# raspberry.net
KiCad netlist of a schematic drawn in EAGLE
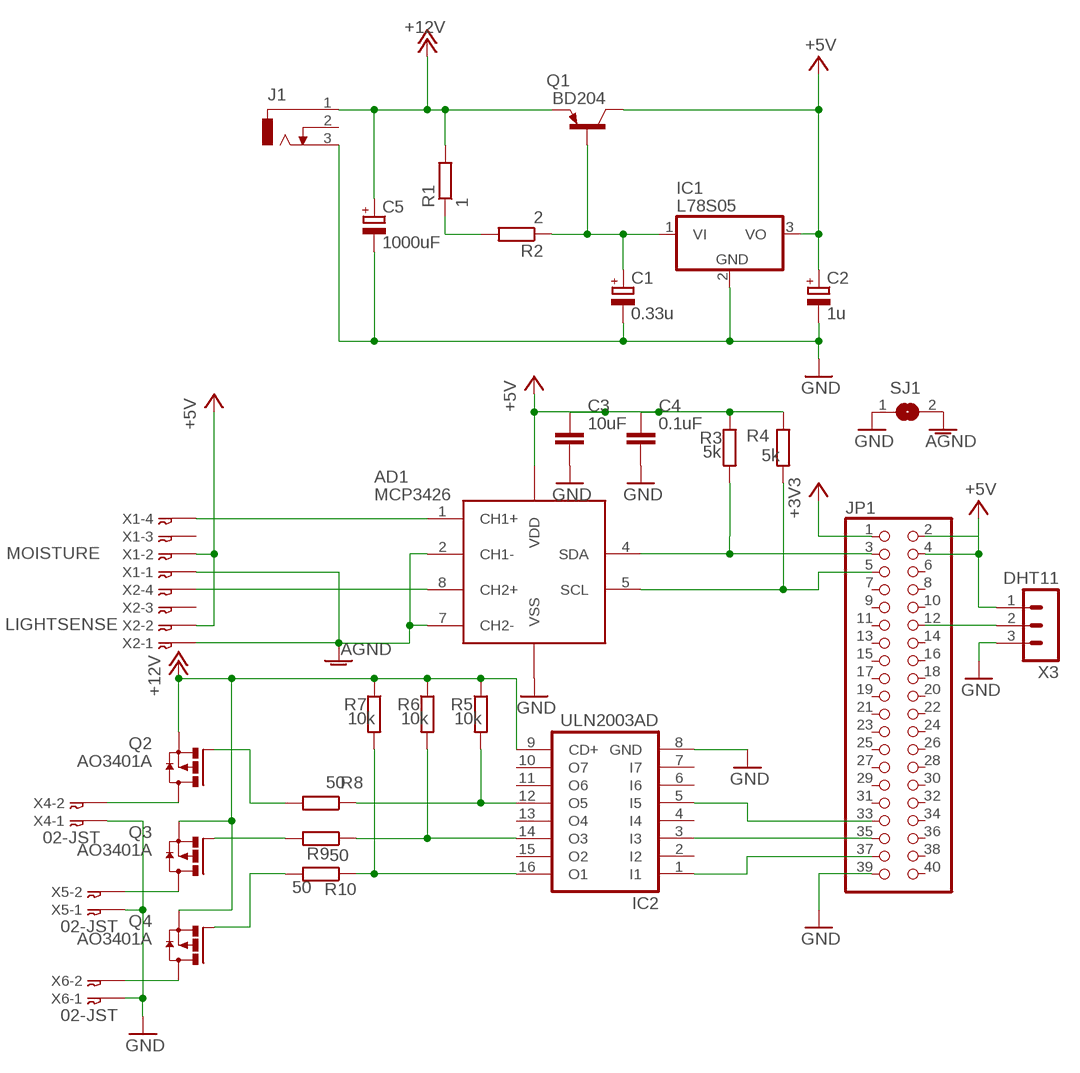
[diagram p0: schematic, sheet 1]

(export (version "E")
  (design (tool "Eeschema 10.0.6"))
  (components
    (comp (ref "AD1")
      (value "MCP3426")
      (footprint "eagle-import:SO-8")
      (libsource (lib "eagle-import") (part "MCP3426A0-E/SN"))
    )
    (comp (ref "C1")
      (value "0.33u")
      (footprint "eagle-import:E1,8-4")
      (libsource (lib "eagle-import") (part "CPOL-EUE1.8-4"))
    )
    (comp (ref "C2")
      (value "1u")
      (footprint "eagle-import:E2-4")
      (libsource (lib "eagle-import") (part "CPOL-EUE2-4"))
    )
    (comp (ref "C3")
      (value "10uF")
      (footprint "eagle-import:CAPM3216X180")
      (libsource (lib "eagle-import") (part "CTANTALUM-1206(3216-METRIC)_"))
    )
    (comp (ref "C4")
      (value "0.1uF")
      (footprint "eagle-import:CAPC2012X110")
      (libsource (lib "eagle-import") (part "CCHIP-0805(2012-METRIC)_"))
    )
    (comp (ref "C5")
      (value "1000uF")
      (footprint "eagle-import:E5-13")
      (libsource (lib "eagle-import") (part "CPOL-EUE5-13"))
    )
    (comp (ref "IC1")
      (value "L78S05")
      (footprint "eagle-import:TO220V")
      (libsource (lib "eagle-import") (part "78TV05"))
    )
    (comp (ref "IC2")
      (value "ULN2003AD")
      (footprint "eagle-import:SO16")
      (libsource (lib "eagle-import") (part "ULN2003AD"))
    )
    (comp (ref "J1")
      (value "DCJ0303")
      (footprint "eagle-import:DCJ0303")
      (libsource (lib "eagle-import") (part "DCJ0303"))
    )
    (comp (ref "JP1")
      (value "PINHD-2X20")
      (footprint "eagle-import:2X20")
      (libsource (lib "eagle-import") (part "PINHD-2X20"))
    )
    (comp (ref "Q1")
      (value "BD204")
      (footprint "eagle-import:TO220V")
      (libsource (lib "eagle-import") (part "-PNP-TO220V"))
    )
    (comp (ref "Q2")
      (value "AO3401A")
      (footprint "eagle-import:SOT23")
      (libsource (lib "eagle-import") (part "AO3401A"))
    )
    (comp (ref "Q3")
      (value "AO3401A")
      (footprint "eagle-import:SOT23")
      (libsource (lib "eagle-import") (part "AO3401A"))
    )
    (comp (ref "Q4")
      (value "AO3401A")
      (footprint "eagle-import:SOT23")
      (libsource (lib "eagle-import") (part "AO3401A"))
    )
    (comp (ref "R1")
      (value "1")
      (footprint "eagle-import:R0805W")
      (libsource (lib "eagle-import") (part "R-EU_R0805W"))
    )
    (comp (ref "R2")
      (value "2")
      (footprint "eagle-import:R0805W")
      (libsource (lib "eagle-import") (part "R-EU_R0805W"))
    )
    (comp (ref "R3")
      (value "5k")
      (footprint "eagle-import:R0805W")
      (libsource (lib "eagle-import") (part "R-EU_R0805W"))
    )
    (comp (ref "R4")
      (value "5k")
      (footprint "eagle-import:R0805W")
      (libsource (lib "eagle-import") (part "R-EU_R0805W"))
    )
    (comp (ref "R5")
      (value "10k")
      (footprint "eagle-import:R0805W")
      (libsource (lib "eagle-import") (part "R-EU_R0805W"))
    )
    (comp (ref "R6")
      (value "10k")
      (footprint "eagle-import:R0805W")
      (libsource (lib "eagle-import") (part "R-EU_R0805W"))
    )
    (comp (ref "R7")
      (value "10k")
      (footprint "eagle-import:R0805W")
      (libsource (lib "eagle-import") (part "R-EU_R0805W"))
    )
    (comp (ref "R8")
      (value "50")
      (footprint "eagle-import:R0805W")
      (libsource (lib "eagle-import") (part "R-EU_R0805W"))
    )
    (comp (ref "R9")
      (value "50")
      (footprint "eagle-import:R0805W")
      (libsource (lib "eagle-import") (part "R-EU_R0805W"))
    )
    (comp (ref "R10")
      (value "50")
      (footprint "eagle-import:R0805W")
      (libsource (lib "eagle-import") (part "R-EU_R0805W"))
    )
    (comp (ref "SJ1") (value "SJ") (footprint "eagle-import:SJ") (libsource (lib "eagle-import") (part "SJ")))
    (comp (ref "X1")
      (value "MOISTURE")
      (footprint "eagle-import:B4B-XH")
      (libsource (lib "eagle-import") (part "04-JST-B4B-XH-A"))
    )
    (comp (ref "X2")
      (value "LIGHTSENSE")
      (footprint "eagle-import:B4B-XH")
      (libsource (lib "eagle-import") (part "04-JST-B4B-XH-A"))
    )
    (comp (ref "X3")
      (value "DHT11")
      (footprint "eagle-import:MA03-1")
      (libsource (lib "eagle-import") (part "MA03-1"))
    )
    (comp (ref "X4")
      (value "02-JST")
      (footprint "eagle-import:B2B-XH")
      (libsource (lib "eagle-import") (part "02-JST"))
    )
    (comp (ref "X5")
      (value "02-JST")
      (footprint "eagle-import:B2B-XH")
      (libsource (lib "eagle-import") (part "02-JST"))
    )
    (comp (ref "X6")
      (value "02-JST")
      (footprint "eagle-import:B2B-XH")
      (libsource (lib "eagle-import") (part "02-JST"))
    )
  )
  (nets
    (net (code "1") (name "+3V3") (class "Default")
      (node (ref "JP1") (pin "1") (pinfunction "1_1") (pintype "passive"))
    )
    (net (code "2") (name "+5V") (class "Default")
      (node (ref "AD1") (pin "3") (pinfunction "VDD_3") (pintype "power_in"))
      (node (ref "C2") (pin "+") (pinfunction "+_+") (pintype "passive"))
      (node (ref "C3") (pin "1") (pinfunction "1_1") (pintype "passive"))
      (node (ref "C4") (pin "1") (pinfunction "1_1") (pintype "passive"))
      (node (ref "IC1") (pin "3") (pinfunction "VO_3") (pintype "passive"))
      (node (ref "JP1") (pin "2") (pinfunction "2_2") (pintype "passive"))
      (node (ref "JP1") (pin "4") (pinfunction "4_4") (pintype "passive"))
      (node (ref "Q1") (pin "2") (pinfunction "C_2") (pintype "passive"))
      (node (ref "R3") (pin "1") (pinfunction "1_1") (pintype "passive"))
      (node (ref "R4") (pin "1") (pinfunction "1_1") (pintype "passive"))
      (node (ref "X1") (pin "P$2") (pinfunction "1_P$2") (pintype "passive"))
      (node (ref "X2") (pin "P$2") (pinfunction "1_P$2") (pintype "passive"))
      (node (ref "X3") (pin "1") (pinfunction "1_1") (pintype "passive"))
    )
    (net (code "3") (name "+12V") (class "Default")
      (node (ref "C5") (pin "+") (pinfunction "+_+") (pintype "passive"))
      (node (ref "IC2") (pin "9") (pinfunction "CD+_9") (pintype "passive"))
      (node (ref "J1") (pin "1") (pinfunction "1_1") (pintype "passive"))
      (node (ref "Q1") (pin "3") (pinfunction "E_3") (pintype "passive"))
      (node (ref "Q2") (pin "2") (pinfunction "S_2") (pintype "passive"))
      (node (ref "Q3") (pin "2") (pinfunction "S_2") (pintype "passive"))
      (node (ref "Q4") (pin "2") (pinfunction "S_2") (pintype "passive"))
      (node (ref "R1") (pin "2") (pinfunction "2_2") (pintype "passive"))
      (node (ref "R5") (pin "1") (pinfunction "1_1") (pintype "passive"))
      (node (ref "R6") (pin "1") (pinfunction "1_1") (pintype "passive"))
      (node (ref "R7") (pin "1") (pinfunction "1_1") (pintype "passive"))
    )
    (net (code "4") (name "AGND") (class "Default")
      (node (ref "AD1") (pin "2") (pinfunction "CH1-_2") (pintype "bidirectional"))
      (node (ref "AD1") (pin "7") (pinfunction "CH2-_7") (pintype "bidirectional"))
      (node (ref "SJ1") (pin "2") (pinfunction "2_2") (pintype "passive"))
      (node (ref "X1") (pin "P$1") (pinfunction "1_P$1") (pintype "passive"))
      (node (ref "X2") (pin "P$1") (pinfunction "1_P$1") (pintype "passive"))
    )
    (net (code "5") (name "GND") (class "Default")
      (node (ref "AD1") (pin "6") (pinfunction "VSS_6") (pintype "power_in"))
      (node (ref "C1") (pin "-") (pinfunction "-_-") (pintype "passive"))
      (node (ref "C2") (pin "-") (pinfunction "-_-") (pintype "passive"))
      (node (ref "C3") (pin "2") (pinfunction "2_2") (pintype "passive"))
      (node (ref "C4") (pin "2") (pinfunction "2_2") (pintype "passive"))
      (node (ref "C5") (pin "-") (pinfunction "-_-") (pintype "passive"))
      (node (ref "IC1") (pin "2") (pinfunction "GND_2") (pintype "passive"))
      (node (ref "IC2") (pin "8") (pinfunction "GND_8") (pintype "power_in"))
      (node (ref "J1") (pin "3") (pinfunction "3_3") (pintype "passive"))
      (node (ref "JP1") (pin "39") (pinfunction "39_39") (pintype "passive"))
      (node (ref "SJ1") (pin "1") (pinfunction "1_1") (pintype "passive"))
      (node (ref "X3") (pin "3") (pinfunction "3_3") (pintype "passive"))
      (node (ref "X4") (pin "P$1") (pinfunction "1_P$1") (pintype "passive"))
      (node (ref "X5") (pin "P$1") (pinfunction "1_P$1") (pintype "passive"))
      (node (ref "X6") (pin "P$1") (pinfunction "1_P$1") (pintype "passive"))
    )
    (net (code "6") (name "Net-(AD1-CH1+)") (class "Default")
      (node (ref "AD1") (pin "1") (pinfunction "CH1+_1") (pintype "bidirectional"))
      (node (ref "X1") (pin "P$4") (pinfunction "1_P$4") (pintype "passive"))
    )
    (net (code "7") (name "Net-(AD1-CH2+)") (class "Default")
      (node (ref "AD1") (pin "8") (pinfunction "CH2+_8") (pintype "bidirectional"))
      (node (ref "X2") (pin "P$4") (pinfunction "1_P$4") (pintype "passive"))
    )
    (net (code "8") (name "Net-(AD1-SCL)") (class "Default")
      (node (ref "AD1") (pin "5") (pinfunction "SCL_5") (pintype "bidirectional"))
      (node (ref "JP1") (pin "5") (pinfunction "5_5") (pintype "passive"))
      (node (ref "R4") (pin "2") (pinfunction "2_2") (pintype "passive"))
    )
    (net (code "9") (name "Net-(AD1-SDA)") (class "Default")
      (node (ref "AD1") (pin "4") (pinfunction "SDA_4") (pintype "bidirectional"))
      (node (ref "JP1") (pin "3") (pinfunction "3_3") (pintype "passive"))
      (node (ref "R3") (pin "2") (pinfunction "2_2") (pintype "passive"))
    )
    (net (code "10") (name "Net-(IC1-VI)") (class "Default")
      (node (ref "C1") (pin "+") (pinfunction "+_+") (pintype "passive"))
      (node (ref "IC1") (pin "1") (pinfunction "VI_1") (pintype "input"))
      (node (ref "Q1") (pin "1") (pinfunction "B_1") (pintype "passive"))
      (node (ref "R2") (pin "1") (pinfunction "1_1") (pintype "passive"))
    )
    (net (code "11") (name "Net-(IC2-I1)") (class "Default")
      (node (ref "IC2") (pin "1") (pinfunction "I1_1") (pintype "input"))
      (node (ref "JP1") (pin "37") (pinfunction "37_37") (pintype "passive"))
    )
    (net (code "12") (name "Net-(IC2-I3)") (class "Default")
      (node (ref "IC2") (pin "3") (pinfunction "I3_3") (pintype "input"))
      (node (ref "JP1") (pin "35") (pinfunction "35_35") (pintype "passive"))
    )
    (net (code "13") (name "Net-(IC2-I5)") (class "Default")
      (node (ref "IC2") (pin "5") (pinfunction "I5_5") (pintype "input"))
      (node (ref "JP1") (pin "33") (pinfunction "33_33") (pintype "passive"))
    )
    (net (code "14") (name "Net-(IC2-O1)") (class "Default")
      (node (ref "IC2") (pin "16") (pinfunction "O1_16") (pintype "open_collector"))
      (node (ref "R10") (pin "1") (pinfunction "1_1") (pintype "passive"))
      (node (ref "R7") (pin "2") (pinfunction "2_2") (pintype "passive"))
    )
    (net (code "15") (name "Net-(IC2-O3)") (class "Default")
      (node (ref "IC2") (pin "14") (pinfunction "O3_14") (pintype "open_collector"))
      (node (ref "R6") (pin "2") (pinfunction "2_2") (pintype "passive"))
      (node (ref "R9") (pin "1") (pinfunction "1_1") (pintype "passive"))
    )
    (net (code "16") (name "Net-(IC2-O5)") (class "Default")
      (node (ref "IC2") (pin "12") (pinfunction "O5_12") (pintype "open_collector"))
      (node (ref "R5") (pin "2") (pinfunction "2_2") (pintype "passive"))
      (node (ref "R8") (pin "1") (pinfunction "1_1") (pintype "passive"))
    )
    (net (code "17") (name "Net-(JP1-Pad12)") (class "Default")
      (node (ref "JP1") (pin "12") (pinfunction "12_12") (pintype "passive"))
      (node (ref "X3") (pin "2") (pinfunction "2_2") (pintype "passive"))
    )
    (net (code "18") (name "Net-(Q2-D)") (class "Default")
      (node (ref "Q2") (pin "3") (pinfunction "D_3") (pintype "passive"))
      (node (ref "X4") (pin "P$2") (pinfunction "1_P$2") (pintype "passive"))
    )
    (net (code "19") (name "Net-(Q2-G)") (class "Default")
      (node (ref "Q2") (pin "1") (pinfunction "G_1") (pintype "passive"))
      (node (ref "R8") (pin "2") (pinfunction "2_2") (pintype "passive"))
    )
    (net (code "20") (name "Net-(Q3-D)") (class "Default")
      (node (ref "Q3") (pin "3") (pinfunction "D_3") (pintype "passive"))
      (node (ref "X5") (pin "P$2") (pinfunction "1_P$2") (pintype "passive"))
    )
    (net (code "21") (name "Net-(Q3-G)") (class "Default")
      (node (ref "Q3") (pin "1") (pinfunction "G_1") (pintype "passive"))
      (node (ref "R9") (pin "2") (pinfunction "2_2") (pintype "passive"))
    )
    (net (code "22") (name "Net-(Q4-D)") (class "Default")
      (node (ref "Q4") (pin "3") (pinfunction "D_3") (pintype "passive"))
      (node (ref "X6") (pin "P$2") (pinfunction "1_P$2") (pintype "passive"))
    )
    (net (code "23") (name "Net-(Q4-G)") (class "Default")
      (node (ref "Q4") (pin "1") (pinfunction "G_1") (pintype "passive"))
      (node (ref "R10") (pin "2") (pinfunction "2_2") (pintype "passive"))
    )
    (net (code "24") (name "Net-(R1-Pad1)") (class "Default")
      (node (ref "R1") (pin "1") (pinfunction "1_1") (pintype "passive"))
      (node (ref "R2") (pin "2") (pinfunction "2_2") (pintype "passive"))
    )
    (net (code "25") (name "unconnected-(IC2-I2-Pad2)") (class "Default")
      (node (ref "IC2") (pin "2") (pinfunction "I2_2") (pintype "input"))
    )
    (net (code "26") (name "unconnected-(IC2-I4-Pad4)") (class "Default")
      (node (ref "IC2") (pin "4") (pinfunction "I4_4") (pintype "input"))
    )
    (net (code "27") (name "unconnected-(IC2-I6-Pad6)") (class "Default")
      (node (ref "IC2") (pin "6") (pinfunction "I6_6") (pintype "input"))
    )
    (net (code "28") (name "unconnected-(IC2-I7-Pad7)") (class "Default")
      (node (ref "IC2") (pin "7") (pinfunction "I7_7") (pintype "input"))
    )
    (net (code "29") (name "unconnected-(IC2-O2-Pad15)") (class "Default")
      (node (ref "IC2") (pin "15") (pinfunction "O2_15") (pintype "open_collector"))
    )
    (net (code "30") (name "unconnected-(IC2-O4-Pad13)") (class "Default")
      (node (ref "IC2") (pin "13") (pinfunction "O4_13") (pintype "open_collector"))
    )
    (net (code "31") (name "unconnected-(IC2-O6-Pad11)") (class "Default")
      (node (ref "IC2") (pin "11") (pinfunction "O6_11") (pintype "open_collector"))
    )
    (net (code "32") (name "unconnected-(IC2-O7-Pad10)") (class "Default")
      (node (ref "IC2") (pin "10") (pinfunction "O7_10") (pintype "open_collector"))
    )
    (net (code "33") (name "unconnected-(J1-Pad2)") (class "Default")
      (node (ref "J1") (pin "2") (pinfunction "2_2") (pintype "passive"))
    )
    (net (code "34") (name "unconnected-(JP1-Pad6)") (class "Default")
      (node (ref "JP1") (pin "6") (pinfunction "6_6") (pintype "passive"))
    )
    (net (code "35") (name "unconnected-(JP1-Pad7)") (class "Default")
      (node (ref "JP1") (pin "7") (pinfunction "7_7") (pintype "passive"))
    )
    (net (code "36") (name "unconnected-(JP1-Pad8)") (class "Default")
      (node (ref "JP1") (pin "8") (pinfunction "8_8") (pintype "passive"))
    )
    (net (code "37") (name "unconnected-(JP1-Pad9)") (class "Default")
      (node (ref "JP1") (pin "9") (pinfunction "9_9") (pintype "passive"))
    )
    (net (code "38") (name "unconnected-(JP1-Pad10)") (class "Default")
      (node (ref "JP1") (pin "10") (pinfunction "10_10") (pintype "passive"))
    )
    (net (code "39") (name "unconnected-(JP1-Pad11)") (class "Default")
      (node (ref "JP1") (pin "11") (pinfunction "11_11") (pintype "passive"))
    )
    (net (code "40") (name "unconnected-(JP1-Pad13)") (class "Default")
      (node (ref "JP1") (pin "13") (pinfunction "13_13") (pintype "passive"))
    )
    (net (code "41") (name "unconnected-(JP1-Pad14)") (class "Default")
      (node (ref "JP1") (pin "14") (pinfunction "14_14") (pintype "passive"))
    )
    (net (code "42") (name "unconnected-(JP1-Pad15)") (class "Default")
      (node (ref "JP1") (pin "15") (pinfunction "15_15") (pintype "passive"))
    )
    (net (code "43") (name "unconnected-(JP1-Pad16)") (class "Default")
      (node (ref "JP1") (pin "16") (pinfunction "16_16") (pintype "passive"))
    )
    (net (code "44") (name "unconnected-(JP1-Pad17)") (class "Default")
      (node (ref "JP1") (pin "17") (pinfunction "17_17") (pintype "passive"))
    )
    (net (code "45") (name "unconnected-(JP1-Pad18)") (class "Default")
      (node (ref "JP1") (pin "18") (pinfunction "18_18") (pintype "passive"))
    )
    (net (code "46") (name "unconnected-(JP1-Pad19)") (class "Default")
      (node (ref "JP1") (pin "19") (pinfunction "19_19") (pintype "passive"))
    )
    (net (code "47") (name "unconnected-(JP1-Pad20)") (class "Default")
      (node (ref "JP1") (pin "20") (pinfunction "20_20") (pintype "passive"))
    )
    (net (code "48") (name "unconnected-(JP1-Pad21)") (class "Default")
      (node (ref "JP1") (pin "21") (pinfunction "21_21") (pintype "passive"))
    )
    (net (code "49") (name "unconnected-(JP1-Pad22)") (class "Default")
      (node (ref "JP1") (pin "22") (pinfunction "22_22") (pintype "passive"))
    )
    (net (code "50") (name "unconnected-(JP1-Pad23)") (class "Default")
      (node (ref "JP1") (pin "23") (pinfunction "23_23") (pintype "passive"))
    )
    (net (code "51") (name "unconnected-(JP1-Pad24)") (class "Default")
      (node (ref "JP1") (pin "24") (pinfunction "24_24") (pintype "passive"))
    )
    (net (code "52") (name "unconnected-(JP1-Pad25)") (class "Default")
      (node (ref "JP1") (pin "25") (pinfunction "25_25") (pintype "passive"))
    )
    (net (code "53") (name "unconnected-(JP1-Pad26)") (class "Default")
      (node (ref "JP1") (pin "26") (pinfunction "26_26") (pintype "passive"))
    )
    (net (code "54") (name "unconnected-(JP1-Pad27)") (class "Default")
      (node (ref "JP1") (pin "27") (pinfunction "27_27") (pintype "passive"))
    )
    (net (code "55") (name "unconnected-(JP1-Pad28)") (class "Default")
      (node (ref "JP1") (pin "28") (pinfunction "28_28") (pintype "passive"))
    )
    (net (code "56") (name "unconnected-(JP1-Pad29)") (class "Default")
      (node (ref "JP1") (pin "29") (pinfunction "29_29") (pintype "passive"))
    )
    (net (code "57") (name "unconnected-(JP1-Pad30)") (class "Default")
      (node (ref "JP1") (pin "30") (pinfunction "30_30") (pintype "passive"))
    )
    (net (code "58") (name "unconnected-(JP1-Pad31)") (class "Default")
      (node (ref "JP1") (pin "31") (pinfunction "31_31") (pintype "passive"))
    )
    (net (code "59") (name "unconnected-(JP1-Pad32)") (class "Default")
      (node (ref "JP1") (pin "32") (pinfunction "32_32") (pintype "passive"))
    )
    (net (code "60") (name "unconnected-(JP1-Pad34)") (class "Default")
      (node (ref "JP1") (pin "34") (pinfunction "34_34") (pintype "passive"))
    )
    (net (code "61") (name "unconnected-(JP1-Pad36)") (class "Default")
      (node (ref "JP1") (pin "36") (pinfunction "36_36") (pintype "passive"))
    )
    (net (code "62") (name "unconnected-(JP1-Pad38)") (class "Default")
      (node (ref "JP1") (pin "38") (pinfunction "38_38") (pintype "passive"))
    )
    (net (code "63") (name "unconnected-(JP1-Pad40)") (class "Default")
      (node (ref "JP1") (pin "40") (pinfunction "40_40") (pintype "passive"))
    )
    (net (code "64") (name "unconnected-(X1C-1-PadP$3)") (class "Default")
      (node (ref "X1") (pin "P$3") (pinfunction "1_P$3") (pintype "passive"))
    )
    (net (code "65") (name "unconnected-(X2C-1-PadP$3)") (class "Default")
      (node (ref "X2") (pin "P$3") (pinfunction "1_P$3") (pintype "passive"))
    )
  )
)
